# motorthing-tmcm-1110.net
KiCad netlist of a schematic drawn in EAGLE
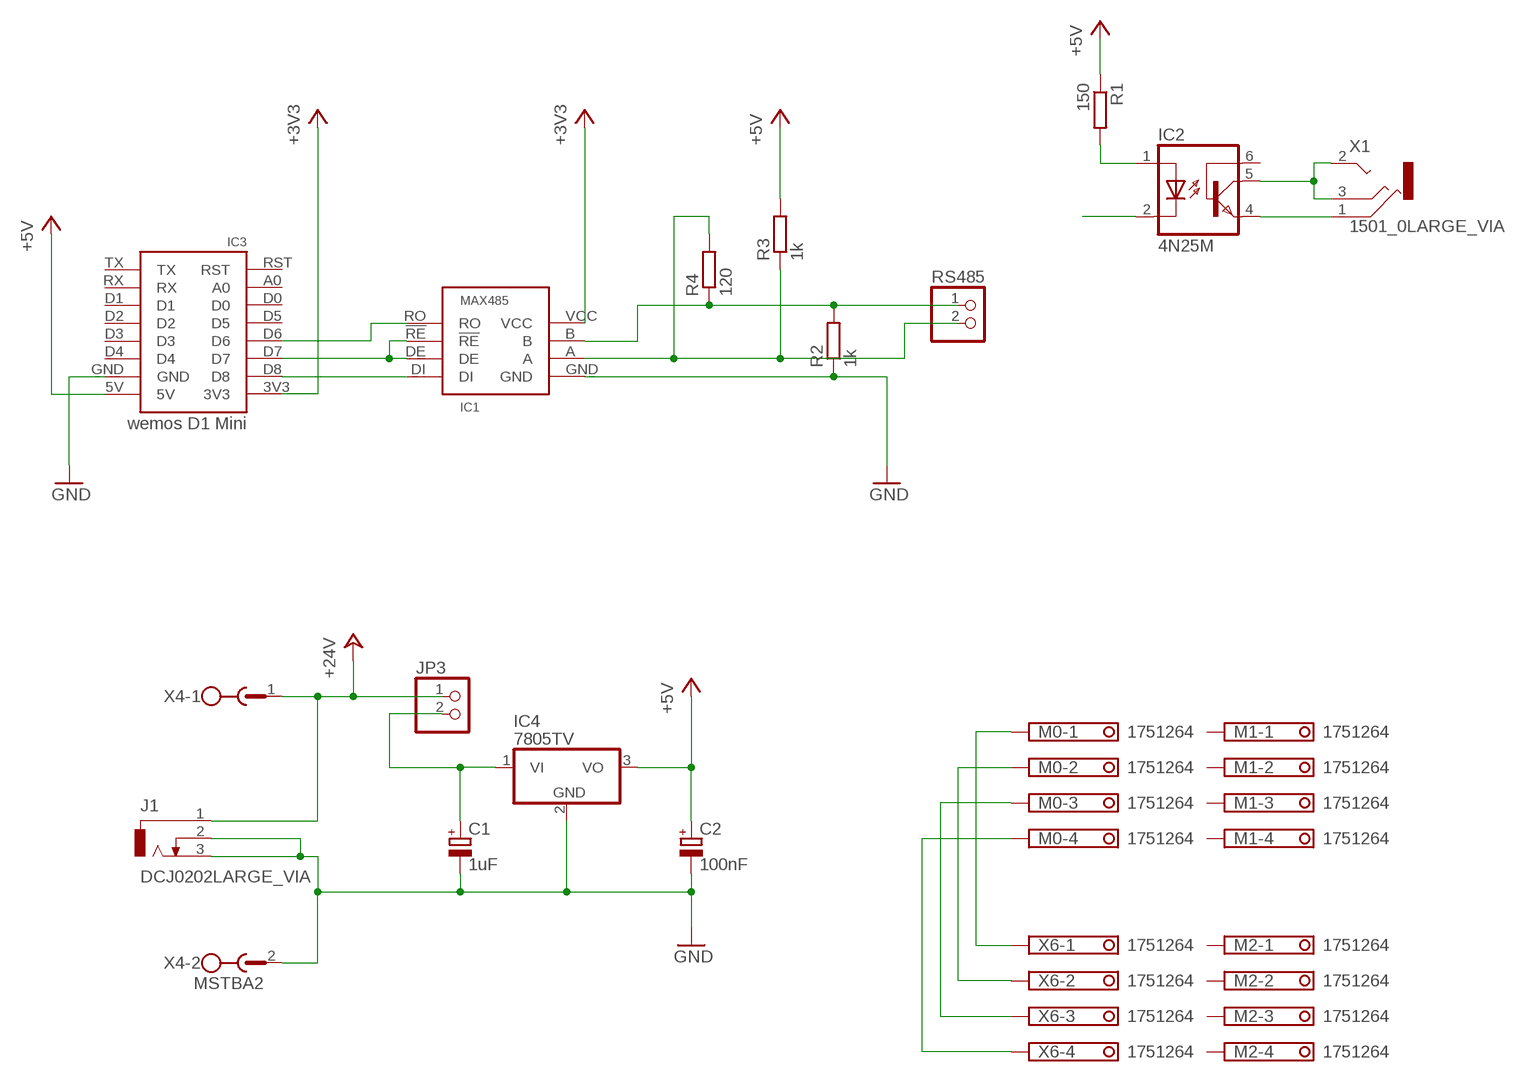
[diagram p0: schematic, sheet 1]

(export (version "E")
  (design (tool "Eeschema 10.0.6"))
  (components
    (comp (ref "C1")
      (value "1uF")
      (footprint "eagle-import:TT2D6")
      (libsource (lib "eagle-import") (part "CPOL-EUTT2D6"))
    )
    (comp (ref "C2")
      (value "100nF")
      (footprint "eagle-import:TT2D5")
      (libsource (lib "eagle-import") (part "CPOL-EUTT2D5"))
    )
    (comp (ref "IC1")
      (value "MAX485")
      (footprint "eagle-import:DIL08")
      (libsource (lib "eagle-import") (part "MAX485"))
    )
    (comp (ref "IC2")
      (value "4N25M")
      (footprint "eagle-import:DIL06")
      (fields (field (name "MPN") "4N25-M"))
      (libsource (lib "eagle-import") (part "4N?M25"))
    )
    (comp (ref "IC3")
      (value "wemos D1 Mini")
      (footprint "eagle-import:WEMOS-NOSILK")
      (libsource (lib "eagle-import") (part "WEMOSNOSILK"))
    )
    (comp (ref "IC4")
      (value "7805TV")
      (footprint "eagle-import:TO220V")
      (libsource (lib "eagle-import") (part "78TV05"))
    )
    (comp (ref "J1")
      (value "DCJ0202LARGE_VIA")
      (footprint "eagle-import:DCJ0202_LV")
      (libsource (lib "eagle-import") (part "DCJ0202LARGE_VIA"))
    )
    (comp (ref "JP3")
      (value "PINHD-1X2")
      (footprint "eagle-import:1X02")
      (libsource (lib "eagle-import") (part "PINHD-1X2"))
    )
    (comp (ref "M0")
      (value "1751264")
      (footprint "eagle-import:1751264")
      (libsource (lib "eagle-import") (part "1751264"))
    )
    (comp (ref "M1")
      (value "1751264")
      (footprint "eagle-import:1751264")
      (libsource (lib "eagle-import") (part "1751264"))
    )
    (comp (ref "M2")
      (value "1751264")
      (footprint "eagle-import:1751264")
      (libsource (lib "eagle-import") (part "1751264"))
    )
    (comp (ref "R1")
      (value "150")
      (footprint "eagle-import:0207_10")
      (libsource (lib "eagle-import") (part "R-EU_0207/10"))
    )
    (comp (ref "R2")
      (value "1k")
      (footprint "eagle-import:0207_10")
      (libsource (lib "eagle-import") (part "R-EU_0207/10"))
    )
    (comp (ref "R3")
      (value "1k")
      (footprint "eagle-import:0207_10")
      (libsource (lib "eagle-import") (part "R-EU_0207/10"))
    )
    (comp (ref "R4")
      (value "120")
      (footprint "eagle-import:0207_10")
      (libsource (lib "eagle-import") (part "R-EU_0207/10"))
    )
    (comp (ref "RS485")
      (value "PINHD-1X2")
      (footprint "eagle-import:1X02")
      (libsource (lib "eagle-import") (part "PINHD-1X2"))
    )
    (comp (ref "X1")
      (value "1501_0LARGE_VIA")
      (footprint "eagle-import:1501_05_LV")
      (libsource (lib "eagle-import") (part "1501_0LARGE_VIA"))
    )
    (comp (ref "X4")
      (value "MSTBA2")
      (footprint "eagle-import:MSTBA2")
      (fields (field (name "MF") "FARNELL") (field (name "MPN") "1757242"))
      (libsource (lib "eagle-import") (part "MSTBA2"))
    )
    (comp (ref "X6")
      (value "1751264")
      (footprint "eagle-import:1751264")
      (libsource (lib "eagle-import") (part "1751264"))
    )
  )
  (nets
    (net (code "1") (name "+3V3") (class "Default")
      (node (ref "IC1") (pin "VCC") (pinfunction "VCC_VCC") (pintype "bidirectional"))
      (node (ref "IC3") (pin "3V3") (pinfunction "3V3_3V3") (pintype "bidirectional"))
    )
    (net (code "2") (name "+5V") (class "Default")
      (node (ref "C2") (pin "+") (pinfunction "+_+") (pintype "passive"))
      (node (ref "IC3") (pin "5V") (pinfunction "5V_5V") (pintype "bidirectional"))
      (node (ref "IC4") (pin "3") (pinfunction "VO_3") (pintype "passive"))
      (node (ref "R1") (pin "1") (pinfunction "1_1") (pintype "passive"))
      (node (ref "R3") (pin "2") (pinfunction "2_2") (pintype "passive"))
    )
    (net (code "3") (name "+24V") (class "Default")
      (node (ref "J1") (pin "1") (pinfunction "1_1") (pintype "passive"))
      (node (ref "JP3") (pin "1") (pinfunction "1_1") (pintype "passive"))
      (node (ref "X4") (pin "1") (pinfunction "1_1") (pintype "passive"))
    )
    (net (code "4") (name "GND") (class "Default")
      (node (ref "C1") (pin "-") (pinfunction "-_-") (pintype "passive"))
      (node (ref "C2") (pin "-") (pinfunction "-_-") (pintype "passive"))
      (node (ref "IC1") (pin "GND") (pinfunction "GND_GND") (pintype "bidirectional"))
      (node (ref "IC3") (pin "GND") (pinfunction "GND_GND") (pintype "bidirectional"))
      (node (ref "IC4") (pin "2") (pinfunction "GND_2") (pintype "passive"))
      (node (ref "J1") (pin "2") (pinfunction "2_2") (pintype "passive"))
      (node (ref "J1") (pin "3") (pinfunction "3_3") (pintype "passive"))
      (node (ref "R2") (pin "1") (pinfunction "1_1") (pintype "passive"))
      (node (ref "X4") (pin "2") (pinfunction "1_2") (pintype "passive"))
    )
    (net (code "5") (name "Net-(IC1-PadA)") (class "Default")
      (node (ref "IC1") (pin "A") (pinfunction "A_A") (pintype "bidirectional"))
      (node (ref "R3") (pin "1") (pinfunction "1_1") (pintype "passive"))
      (node (ref "R4") (pin "2") (pinfunction "2_2") (pintype "passive"))
      (node (ref "RS485") (pin "2") (pinfunction "2_2") (pintype "passive"))
    )
    (net (code "6") (name "Net-(IC1-PadB)") (class "Default")
      (node (ref "IC1") (pin "B") (pinfunction "B_B") (pintype "bidirectional"))
      (node (ref "R2") (pin "2") (pinfunction "2_2") (pintype "passive"))
      (node (ref "R4") (pin "1") (pinfunction "1_1") (pintype "passive"))
      (node (ref "RS485") (pin "1") (pinfunction "1_1") (pintype "passive"))
    )
    (net (code "7") (name "Net-(IC1-PadDI)") (class "Default")
      (node (ref "IC1") (pin "DI") (pinfunction "DI_DI") (pintype "bidirectional"))
      (node (ref "IC3") (pin "D8") (pinfunction "D8_D8") (pintype "bidirectional"))
    )
    (net (code "8") (name "Net-(IC1-PadRO)") (class "Default")
      (node (ref "IC1") (pin "RO") (pinfunction "RO_RO") (pintype "bidirectional"))
      (node (ref "IC3") (pin "D6") (pinfunction "D6_D6") (pintype "bidirectional"))
    )
    (net (code "9") (name "Net-(IC1-~{RE})") (class "Default")
      (node (ref "IC1") (pin "!RE") (pinfunction "~{RE}_!RE") (pintype "bidirectional"))
      (node (ref "IC1") (pin "DE") (pinfunction "DE_DE") (pintype "bidirectional"))
      (node (ref "IC3") (pin "D7") (pinfunction "D7_D7") (pintype "bidirectional"))
    )
    (net (code "10") (name "Net-(IC2-A)") (class "Default")
      (node (ref "IC2") (pin "1") (pinfunction "A_1") (pintype "passive"))
      (node (ref "R1") (pin "2") (pinfunction "2_2") (pintype "passive"))
    )
    (net (code "11") (name "Net-(IC2-COL)") (class "Default")
      (node (ref "IC2") (pin "5") (pinfunction "COL_5") (pintype "passive"))
      (node (ref "X1") (pin "2") (pinfunction "2_2") (pintype "passive"))
      (node (ref "X1") (pin "3") (pinfunction "3_3") (pintype "passive"))
    )
    (net (code "12") (name "Net-(IC2-EMI)") (class "Default")
      (node (ref "IC2") (pin "4") (pinfunction "EMI_4") (pintype "passive"))
      (node (ref "X1") (pin "1") (pinfunction "1_1") (pintype "passive"))
    )
    (net (code "13") (name "Net-(IC4-VI)") (class "Default")
      (node (ref "C1") (pin "+") (pinfunction "+_+") (pintype "passive"))
      (node (ref "IC4") (pin "1") (pinfunction "VI_1") (pintype "input"))
      (node (ref "JP3") (pin "2") (pinfunction "2_2") (pintype "passive"))
    )
    (net (code "14") (name "Net-(M0A-K)") (class "Default")
      (node (ref "M0") (pin "1") (pinfunction "K_1") (pintype "passive"))
      (node (ref "X6") (pin "1") (pinfunction "K_1") (pintype "passive"))
    )
    (net (code "15") (name "Net-(M0B-K)") (class "Default")
      (node (ref "M0") (pin "2") (pinfunction "K_2") (pintype "passive"))
      (node (ref "X6") (pin "2") (pinfunction "K_2") (pintype "passive"))
    )
    (net (code "16") (name "Net-(M0C-K)") (class "Default")
      (node (ref "M0") (pin "3") (pinfunction "K_3") (pintype "passive"))
      (node (ref "X6") (pin "3") (pinfunction "K_3") (pintype "passive"))
    )
    (net (code "17") (name "Net-(M0D-K)") (class "Default")
      (node (ref "M0") (pin "4") (pinfunction "K_4") (pintype "passive"))
      (node (ref "X6") (pin "4") (pinfunction "K_4") (pintype "passive"))
    )
    (net (code "18") (name "unconnected-(IC2-BAS-Pad6)") (class "Default")
      (node (ref "IC2") (pin "6") (pinfunction "BAS_6") (pintype "passive"))
    )
    (net (code "19") (name "unconnected-(IC2-C-Pad2)") (class "Default")
      (node (ref "IC2") (pin "2") (pinfunction "C_2") (pintype "passive"))
    )
    (net (code "20") (name "unconnected-(IC3-PadA0)") (class "Default")
      (node (ref "IC3") (pin "A0") (pinfunction "A0_A0") (pintype "bidirectional"))
    )
    (net (code "21") (name "unconnected-(IC3-PadD0)") (class "Default")
      (node (ref "IC3") (pin "D0") (pinfunction "D0_D0") (pintype "bidirectional"))
    )
    (net (code "22") (name "unconnected-(IC3-PadD1)") (class "Default")
      (node (ref "IC3") (pin "D1") (pinfunction "D1_D1") (pintype "bidirectional"))
    )
    (net (code "23") (name "unconnected-(IC3-PadD2)") (class "Default")
      (node (ref "IC3") (pin "D2") (pinfunction "D2_D2") (pintype "bidirectional"))
    )
    (net (code "24") (name "unconnected-(IC3-PadD3)") (class "Default")
      (node (ref "IC3") (pin "D3") (pinfunction "D3_D3") (pintype "bidirectional"))
    )
    (net (code "25") (name "unconnected-(IC3-PadD4)") (class "Default")
      (node (ref "IC3") (pin "D4") (pinfunction "D4_D4") (pintype "bidirectional"))
    )
    (net (code "26") (name "unconnected-(IC3-PadD5)") (class "Default")
      (node (ref "IC3") (pin "D5") (pinfunction "D5_D5") (pintype "bidirectional"))
    )
    (net (code "27") (name "unconnected-(IC3-PadRST)") (class "Default")
      (node (ref "IC3") (pin "RST") (pinfunction "RST_RST") (pintype "bidirectional"))
    )
    (net (code "28") (name "unconnected-(IC3-PadRX)") (class "Default")
      (node (ref "IC3") (pin "RX") (pinfunction "RX_RX") (pintype "bidirectional"))
    )
    (net (code "29") (name "unconnected-(IC3-PadTX)") (class "Default")
      (node (ref "IC3") (pin "TX") (pinfunction "TX_TX") (pintype "bidirectional"))
    )
    (net (code "30") (name "unconnected-(M1A-K-Pad1)") (class "Default")
      (node (ref "M1") (pin "1") (pinfunction "K_1") (pintype "passive"))
    )
    (net (code "31") (name "unconnected-(M1B-K-Pad2)") (class "Default")
      (node (ref "M1") (pin "2") (pinfunction "K_2") (pintype "passive"))
    )
    (net (code "32") (name "unconnected-(M1C-K-Pad3)") (class "Default")
      (node (ref "M1") (pin "3") (pinfunction "K_3") (pintype "passive"))
    )
    (net (code "33") (name "unconnected-(M1D-K-Pad4)") (class "Default")
      (node (ref "M1") (pin "4") (pinfunction "K_4") (pintype "passive"))
    )
    (net (code "34") (name "unconnected-(M2A-K-Pad1)") (class "Default")
      (node (ref "M2") (pin "1") (pinfunction "K_1") (pintype "passive"))
    )
    (net (code "35") (name "unconnected-(M2B-K-Pad2)") (class "Default")
      (node (ref "M2") (pin "2") (pinfunction "K_2") (pintype "passive"))
    )
    (net (code "36") (name "unconnected-(M2C-K-Pad3)") (class "Default")
      (node (ref "M2") (pin "3") (pinfunction "K_3") (pintype "passive"))
    )
    (net (code "37") (name "unconnected-(M2D-K-Pad4)") (class "Default")
      (node (ref "M2") (pin "4") (pinfunction "K_4") (pintype "passive"))
    )
  )
)
